# sheet_top.net
KiCad netlist of a schematic drawn in Altium Designer
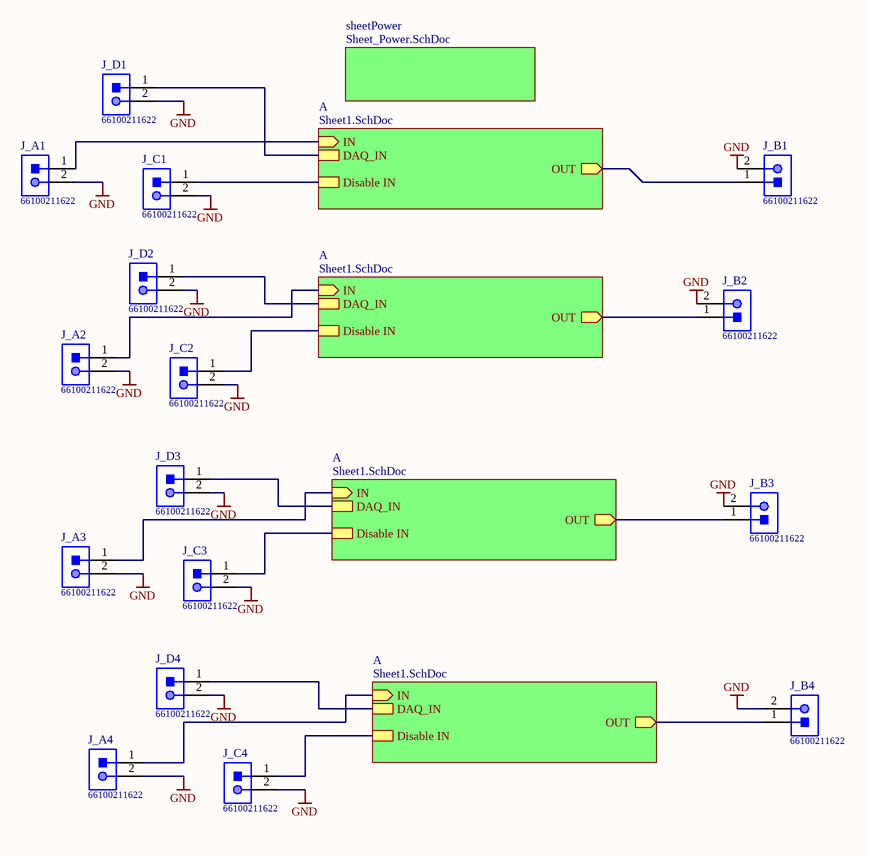
[diagram p0: sheet_top.SchDoc]

(export (version "E")
  (design (tool "Eeschema 10.0.6"))
  (components
    (comp (ref "J_A1")
      (value "66100211622")
      (footprint "66100211622")
      (description "WR-WTB 2.54 mm Male Vertical Shrouded Header 2 Pins")
      (fields (field (name "MANUFACTURER") "Wurth Electronics"))
      (libsource (lib "EMBL") (part "WE-CN-1P-M-R2"))
    )
    (comp (ref "J_A2")
      (value "66100211622")
      (footprint "66100211622")
      (description "WR-WTB 2.54 mm Male Vertical Shrouded Header 2 Pins")
      (fields (field (name "MANUFACTURER") "Wurth Electronics"))
      (libsource (lib "EMBL") (part "WE-CN-1P-M-R2"))
    )
    (comp (ref "J_A3")
      (value "66100211622")
      (footprint "66100211622")
      (description "WR-WTB 2.54 mm Male Vertical Shrouded Header 2 Pins")
      (fields (field (name "MANUFACTURER") "Wurth Electronics"))
      (libsource (lib "EMBL") (part "WE-CN-1P-M-R2"))
    )
    (comp (ref "J_A4")
      (value "66100211622")
      (footprint "66100211622")
      (description "WR-WTB 2.54 mm Male Vertical Shrouded Header 2 Pins")
      (fields (field (name "MANUFACTURER") "Wurth Electronics"))
      (libsource (lib "EMBL") (part "WE-CN-1P-M-R2"))
    )
    (comp (ref "J_B1")
      (value "66100211622")
      (footprint "66100211622")
      (description "WR-WTB 2.54 mm Male Vertical Shrouded Header 2 Pins")
      (fields (field (name "MANUFACTURER") "Wurth Electronics"))
      (libsource (lib "") (part "WE-CN-1P-M-R2_1"))
    )
    (comp (ref "J_B2")
      (value "66100211622")
      (footprint "66100211622")
      (description "WR-WTB 2.54 mm Male Vertical Shrouded Header 2 Pins")
      (fields (field (name "MANUFACTURER") "Wurth Electronics"))
      (libsource (lib "") (part "WE-CN-1P-M-R2_1"))
    )
    (comp (ref "J_B3")
      (value "66100211622")
      (footprint "66100211622")
      (description "WR-WTB 2.54 mm Male Vertical Shrouded Header 2 Pins")
      (fields (field (name "MANUFACTURER") "Wurth Electronics"))
      (libsource (lib "") (part "WE-CN-1P-M-R2_1"))
    )
    (comp (ref "J_B4")
      (value "66100211622")
      (footprint "66100211622")
      (description "WR-WTB 2.54 mm Male Vertical Shrouded Header 2 Pins")
      (fields (field (name "MANUFACTURER") "Wurth Electronics"))
      (libsource (lib "") (part "WE-CN-1P-M-R2_1"))
    )
    (comp (ref "J_C1")
      (value "66100211622")
      (footprint "66100211622")
      (description "WR-WTB 2.54 mm Male Vertical Shrouded Header 2 Pins")
      (fields (field (name "MANUFACTURER") "Wurth Electronics"))
      (libsource (lib "EMBL") (part "WE-CN-1P-M-R2"))
    )
    (comp (ref "J_C2")
      (value "66100211622")
      (footprint "66100211622")
      (description "WR-WTB 2.54 mm Male Vertical Shrouded Header 2 Pins")
      (fields (field (name "MANUFACTURER") "Wurth Electronics"))
      (libsource (lib "EMBL") (part "WE-CN-1P-M-R2"))
    )
    (comp (ref "J_C3")
      (value "66100211622")
      (footprint "66100211622")
      (description "WR-WTB 2.54 mm Male Vertical Shrouded Header 2 Pins")
      (fields (field (name "MANUFACTURER") "Wurth Electronics"))
      (libsource (lib "EMBL") (part "WE-CN-1P-M-R2"))
    )
    (comp (ref "J_C4")
      (value "66100211622")
      (footprint "66100211622")
      (description "WR-WTB 2.54 mm Male Vertical Shrouded Header 2 Pins")
      (fields (field (name "MANUFACTURER") "Wurth Electronics"))
      (libsource (lib "EMBL") (part "WE-CN-1P-M-R2"))
    )
    (comp (ref "J_D1")
      (value "66100211622")
      (footprint "66100211622")
      (description "WR-WTB 2.54 mm Male Vertical Shrouded Header 2 Pins")
      (fields (field (name "MANUFACTURER") "Wurth Electronics"))
      (libsource (lib "EMBL") (part "WE-CN-1P-M-R2"))
    )
    (comp (ref "J_D2")
      (value "66100211622")
      (footprint "66100211622")
      (description "WR-WTB 2.54 mm Male Vertical Shrouded Header 2 Pins")
      (fields (field (name "MANUFACTURER") "Wurth Electronics"))
      (libsource (lib "EMBL") (part "WE-CN-1P-M-R2"))
    )
    (comp (ref "J_D3")
      (value "66100211622")
      (footprint "66100211622")
      (description "WR-WTB 2.54 mm Male Vertical Shrouded Header 2 Pins")
      (fields (field (name "MANUFACTURER") "Wurth Electronics"))
      (libsource (lib "EMBL") (part "WE-CN-1P-M-R2"))
    )
    (comp (ref "J_D4")
      (value "66100211622")
      (footprint "66100211622")
      (description "WR-WTB 2.54 mm Male Vertical Shrouded Header 2 Pins")
      (fields (field (name "MANUFACTURER") "Wurth Electronics"))
      (libsource (lib "EMBL") (part "WE-CN-1P-M-R2"))
    )
  )
  (nets
    (net (code "1") (name "/DAQ_IN") (class "Default")
      (node (ref "J_D1") (pin "1") (pinfunction "1_1") (pintype "passive"))
    )
    (net (code "2") (name "/DAQ_IN_1") (class "Default")
      (node (ref "J_D4") (pin "1") (pinfunction "1_1") (pintype "passive"))
    )
    (net (code "3") (name "/DAQ_IN_2") (class "Default")
      (node (ref "J_D2") (pin "1") (pinfunction "1_1") (pintype "passive"))
    )
    (net (code "4") (name "/DAQ_IN_3") (class "Default")
      (node (ref "J_D3") (pin "1") (pinfunction "1_1") (pintype "passive"))
    )
    (net (code "5") (name "/Disable IN") (class "Default")
      (node (ref "J_C3") (pin "1") (pinfunction "1_1") (pintype "passive"))
    )
    (net (code "6") (name "/Disable IN_1") (class "Default")
      (node (ref "J_C4") (pin "1") (pinfunction "1_1") (pintype "passive"))
    )
    (net (code "7") (name "/Disable IN_2") (class "Default")
      (node (ref "J_C2") (pin "1") (pinfunction "1_1") (pintype "passive"))
    )
    (net (code "8") (name "/Disable IN_3") (class "Default")
      (node (ref "J_C1") (pin "1") (pinfunction "1_1") (pintype "passive"))
    )
    (net (code "9") (name "/IN") (class "Default")
      (node (ref "J_A3") (pin "1") (pinfunction "1_1") (pintype "passive"))
    )
    (net (code "10") (name "/IN_1") (class "Default")
      (node (ref "J_A4") (pin "1") (pinfunction "1_1") (pintype "passive"))
    )
    (net (code "11") (name "/IN_2") (class "Default")
      (node (ref "J_A2") (pin "1") (pinfunction "1_1") (pintype "passive"))
    )
    (net (code "12") (name "/IN_3") (class "Default")
      (node (ref "J_A1") (pin "1") (pinfunction "1_1") (pintype "passive"))
    )
    (net (code "13") (name "/OUT") (class "Default")
      (node (ref "J_B2") (pin "1") (pinfunction "1_1") (pintype "passive"))
    )
    (net (code "14") (name "/OUT_1") (class "Default")
      (node (ref "J_B4") (pin "1") (pinfunction "1_1") (pintype "passive"))
    )
    (net (code "15") (name "/OUT_2") (class "Default")
      (node (ref "J_B3") (pin "1") (pinfunction "1_1") (pintype "passive"))
    )
    (net (code "16") (name "/OUT_3") (class "Default")
      (node (ref "J_B1") (pin "1") (pinfunction "1_1") (pintype "passive"))
    )
    (net (code "17") (name "GND") (class "Default")
      (node (ref "J_A1") (pin "2") (pinfunction "2_2") (pintype "passive"))
      (node (ref "J_A2") (pin "2") (pinfunction "2_2") (pintype "passive"))
      (node (ref "J_A3") (pin "2") (pinfunction "2_2") (pintype "passive"))
      (node (ref "J_A4") (pin "2") (pinfunction "2_2") (pintype "passive"))
      (node (ref "J_B1") (pin "2") (pinfunction "2_2") (pintype "passive"))
      (node (ref "J_B2") (pin "2") (pinfunction "2_2") (pintype "passive"))
      (node (ref "J_B3") (pin "2") (pinfunction "2_2") (pintype "passive"))
      (node (ref "J_B4") (pin "2") (pinfunction "2_2") (pintype "passive"))
      (node (ref "J_C1") (pin "2") (pinfunction "2_2") (pintype "passive"))
      (node (ref "J_C2") (pin "2") (pinfunction "2_2") (pintype "passive"))
      (node (ref "J_C3") (pin "2") (pinfunction "2_2") (pintype "passive"))
      (node (ref "J_C4") (pin "2") (pinfunction "2_2") (pintype "passive"))
      (node (ref "J_D1") (pin "2") (pinfunction "2_2") (pintype "passive"))
      (node (ref "J_D2") (pin "2") (pinfunction "2_2") (pintype "passive"))
      (node (ref "J_D3") (pin "2") (pinfunction "2_2") (pintype "passive"))
      (node (ref "J_D4") (pin "2") (pinfunction "2_2") (pintype "passive"))
    )
  )
)
